# Comm.net
KiCad netlist of a schematic drawn in Altium Designer
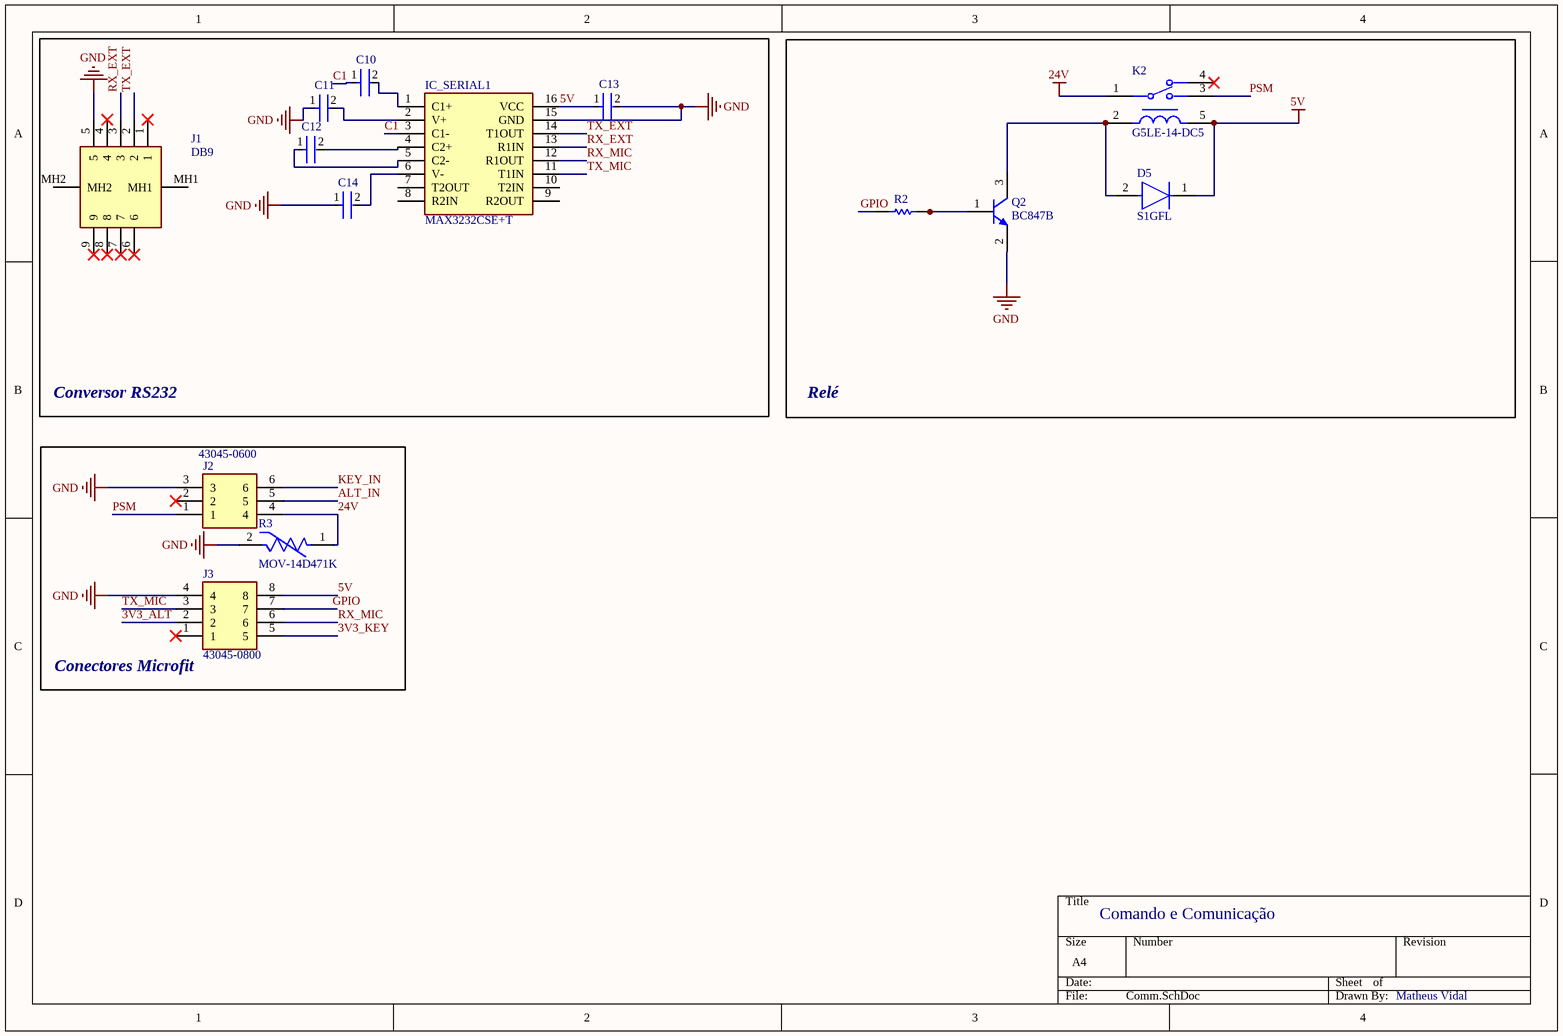
[diagram p0: Comm.SchDoc]

(export (version "E")
  (design (tool "Eeschema 10.0.6"))
  (components
    (comp (ref "C10")
      (value "08055C104J4T2A")
      (footprint "FP-0805-L_2_01_0_2-W_1_25-MFG")
      (description "Automotive Ceramic Capacitor, 0805, 100nF, 5%, X7R, 15%, 50V")
      (fields (field (name "TOLERANCE") "5%"))
      (libsource (lib "Altium Content Vault") (part "02cd4be3c70576c341d710602a673aa"))
    )
    (comp (ref "C11")
      (value "08055C104J4T2A")
      (footprint "FP-0805-L_2_01_0_2-W_1_25-MFG")
      (description "Automotive Ceramic Capacitor, 0805, 100nF, 5%, X7R, 15%, 50V")
      (fields (field (name "TOLERANCE") "5%"))
      (libsource (lib "Altium Content Vault") (part "02cd4be3c70576c341d710602a673aa"))
    )
    (comp (ref "C12")
      (value "08055C104J4T2A")
      (footprint "FP-0805-L_2_01_0_2-W_1_25-MFG")
      (description "Automotive Ceramic Capacitor, 0805, 100nF, 5%, X7R, 15%, 50V")
      (fields (field (name "TOLERANCE") "5%"))
      (libsource (lib "Altium Content Vault") (part "02cd4be3c70576c341d710602a673aa"))
    )
    (comp (ref "C13")
      (value "08055C104J4T2A")
      (footprint "FP-0805-L_2_01_0_2-W_1_25-MFG")
      (description "Automotive Ceramic Capacitor, 0805, 100nF, 5%, X7R, 15%, 50V")
      (fields (field (name "TOLERANCE") "5%"))
      (libsource (lib "Altium Content Vault") (part "02cd4be3c70576c341d710602a673aa"))
    )
    (comp (ref "C14")
      (value "08055C104J4T2A")
      (footprint "FP-0805-L_2_01_0_2-W_1_25-MFG")
      (description "Automotive Ceramic Capacitor, 0805, 100nF, 5%, X7R, 15%, 50V")
      (fields (field (name "TOLERANCE") "5%"))
      (libsource (lib "Altium Content Vault") (part "02cd4be3c70576c341d710602a673aa"))
    )
    (comp (ref "D5")
      (value "S1GFL")
      (footprint "FP-425AD-MFG")
      (description "S1GFL Rectifier Diode, 1 Phase, 1 Element, 1A, 400V V(RRM), Silicon")
      (libsource (lib "Altium Content Vault") (part "e8bb5000357cae87636711d27716c66"))
    )
    (comp (ref "IC_SERIAL1")
      (value "MAX3232CSE+T")
      (footprint "SamacSys:SOIC127P600X175-16N")
      (description "Integrated Circuit")
      (fields (field (name "MOUSER PART NUMBER") "700-MAX3232CSET"))
      (libsource (lib "*") (part "MAX3232CSE+T"))
    )
    (comp (ref "J1")
      (value "DB9")
      (footprint "SamacSys:L77DFE09S1AMN")
      (description "Connector")
      (fields
        (field (name "MANUFACTURER_PART_NUMBER") "L77DFE09S1AMN")
        (field (name "MOUSER PART NUMBER") "523-L77DFE09S1AMN")
      )
      (libsource (lib "*") (part "L77DFE09S1AMN"))
    )
    (comp (ref "J2")
      (value "43045-0600")
      (footprint "SamacSys:43045-06(00,01,02,10)")
      (description "Connector")
      (fields (field (name "MOUSER PART NUMBER") "538-43045-0600"))
      (libsource (lib "*") (part "43045-0600"))
    )
    (comp (ref "J3")
      (value "43045-0800")
      (footprint "SamacSys:43045-08(00,01,02,10)")
      (description "Connector")
      (fields (field (name "MOUSER PART NUMBER") "538-43045-0800"))
      (libsource (lib "*") (part "43045-0800"))
    )
    (comp (ref "K2")
      (value "G5LE-14-DC5")
      (footprint "FP-G5LE-14-DC5-MFG")
      (description "RELAY GEN PURPOSE SPDT 10A 5V")
      (fields
        (field (name "OCTOPART") "https://octopart.com/g5le-14-dc5-omron-28829")
        (field (name "MANUFACTURER") "Omron")
      )
      (libsource (lib "Altium Content Vault") (part "c03b8d08e5d02e70a6880f365e34168"))
    )
    (comp (ref "Q2")
      (value "BC847B")
      (footprint "INF-SOT23_M")
      (description "NPN Silicon AF Transistor, 45 V VCEO, 100 mA IC, SOT23, Reel, Green")
      (fields (field (name "MANUFACTURER") "Infineon"))
      (libsource (lib "Altium Content Vault") (part "INF-BJTNPN-BEC-3"))
    )
    (comp (ref "R2")
      (value "10k")
      (footprint "RESC2013X50X30LL20T20")
      (fields (field (name "MANUFACTURER") "Vishay Dale") (field (name "PART NUMBER") "CRCW08050000Z0EA"))
      (libsource (lib "Altium Content Vault") (part "RES"))
    )
    (comp (ref "R3")
      (value "MOV-14D471K")
      (footprint "FP-MOV-14D471K-MFG")
      (description "VARISTOR 470V 4.5KA DISC 14MM")
      (fields
        (field (name "OCTOPART") "https://octopart.com/mov-14d471k-bourns-21388916")
        (field (name "MANUFACTURER") "Bourns Inc.")
      )
      (libsource (lib "Altium Content Vault") (part "78a88060d5b7b043d6e48adc4284376"))
    )
  )
  (nets
    (net (code "1") (name "/3V3_ALT") (class "Default")
      (node (ref "J3") (pin "2") (pinfunction "2_2") (pintype "passive"))
    )
    (net (code "2") (name "/3V3_KEY") (class "Default")
      (node (ref "J3") (pin "5") (pinfunction "5_5") (pintype "passive"))
    )
    (net (code "3") (name "/ALT_IN") (class "Default")
      (node (ref "J2") (pin "5") (pinfunction "5_5") (pintype "passive"))
    )
    (net (code "4") (name "/C1") (class "Default")
      (node (ref "C10") (pin "1") (pinfunction "1_1") (pintype "passive"))
      (node (ref "IC_SERIAL1") (pin "3") (pinfunction "C1-_3") (pintype "passive"))
    )
    (net (code "5") (name "/GPIO") (class "Default")
      (node (ref "J3") (pin "7") (pinfunction "7_7") (pintype "passive"))
      (node (ref "R2") (pin "2") (pinfunction "2_2") (pintype "passive"))
    )
    (net (code "6") (name "/KEY_IN") (class "Default")
      (node (ref "J2") (pin "6") (pinfunction "6_6") (pintype "passive"))
    )
    (net (code "7") (name "/PSM") (class "Default")
      (node (ref "J2") (pin "1") (pinfunction "1_1") (pintype "passive"))
      (node (ref "K2") (pin "3") (pinfunction "3_3") (pintype "passive"))
    )
    (net (code "8") (name "/RX_EXT") (class "Default")
      (node (ref "IC_SERIAL1") (pin "13") (pinfunction "R1IN_13") (pintype "passive"))
      (node (ref "J1") (pin "3") (pinfunction "3_3") (pintype "passive"))
    )
    (net (code "9") (name "/RX_MIC") (class "Default")
      (node (ref "IC_SERIAL1") (pin "12") (pinfunction "R1OUT_12") (pintype "passive"))
      (node (ref "J3") (pin "6") (pinfunction "6_6") (pintype "passive"))
    )
    (net (code "10") (name "/TX_EXT") (class "Default")
      (node (ref "IC_SERIAL1") (pin "14") (pinfunction "T1OUT_14") (pintype "passive"))
      (node (ref "J1") (pin "2") (pinfunction "2_2") (pintype "passive"))
    )
    (net (code "11") (name "/TX_MIC") (class "Default")
      (node (ref "IC_SERIAL1") (pin "11") (pinfunction "T1IN_11") (pintype "passive"))
      (node (ref "J3") (pin "3") (pinfunction "3_3") (pintype "passive"))
    )
    (net (code "12") (name "5V") (class "Default")
      (node (ref "C13") (pin "1") (pinfunction "1_1") (pintype "passive"))
      (node (ref "D5") (pin "1") (pinfunction "C_1") (pintype "passive"))
      (node (ref "IC_SERIAL1") (pin "16") (pinfunction "VCC_16") (pintype "passive"))
      (node (ref "J3") (pin "8") (pinfunction "8_8") (pintype "passive"))
      (node (ref "K2") (pin "5") (pinfunction "5_5") (pintype "passive"))
    )
    (net (code "13") (name "24V") (class "Default")
      (node (ref "J2") (pin "4") (pinfunction "4_4") (pintype "passive"))
      (node (ref "K2") (pin "1") (pinfunction "1_1") (pintype "passive"))
      (node (ref "R3") (pin "1") (pinfunction "1_1") (pintype "passive"))
    )
    (net (code "14") (name "GND") (class "Default")
      (node (ref "C11") (pin "1") (pinfunction "1_1") (pintype "passive"))
      (node (ref "C13") (pin "2") (pinfunction "2_2") (pintype "passive"))
      (node (ref "C14") (pin "1") (pinfunction "1_1") (pintype "passive"))
      (node (ref "IC_SERIAL1") (pin "15") (pinfunction "GND_15") (pintype "passive"))
      (node (ref "J1") (pin "5") (pinfunction "5_5") (pintype "passive"))
      (node (ref "J2") (pin "3") (pinfunction "3_3") (pintype "passive"))
      (node (ref "J3") (pin "4") (pinfunction "4_4") (pintype "passive"))
      (node (ref "Q2") (pin "2") (pinfunction "E_2") (pintype "passive"))
      (node (ref "R3") (pin "2") (pinfunction "2_2") (pintype "passive"))
    )
    (net (code "15") (name "Net-(D5-A)") (class "Default")
      (node (ref "D5") (pin "2") (pinfunction "A_2") (pintype "passive"))
      (node (ref "K2") (pin "2") (pinfunction "2_2") (pintype "passive"))
      (node (ref "Q2") (pin "3") (pinfunction "C_3") (pintype "passive"))
    )
    (net (code "16") (name "Net-(IC_SERIAL1-C1+)") (class "Default")
      (node (ref "C10") (pin "2") (pinfunction "2_2") (pintype "passive"))
      (node (ref "IC_SERIAL1") (pin "1") (pinfunction "C1+_1") (pintype "passive"))
    )
    (net (code "17") (name "Net-(IC_SERIAL1-C2+)") (class "Default")
      (node (ref "C12") (pin "2") (pinfunction "2_2") (pintype "passive"))
      (node (ref "IC_SERIAL1") (pin "4") (pinfunction "C2+_4") (pintype "passive"))
    )
    (net (code "18") (name "Net-(IC_SERIAL1-C2-)") (class "Default")
      (node (ref "C12") (pin "1") (pinfunction "1_1") (pintype "passive"))
      (node (ref "IC_SERIAL1") (pin "5") (pinfunction "C2-_5") (pintype "passive"))
    )
    (net (code "19") (name "Net-(IC_SERIAL1-V+)") (class "Default")
      (node (ref "C11") (pin "2") (pinfunction "2_2") (pintype "passive"))
      (node (ref "IC_SERIAL1") (pin "2") (pinfunction "V+_2") (pintype "passive"))
    )
    (net (code "20") (name "Net-(IC_SERIAL1-V-)") (class "Default")
      (node (ref "C14") (pin "2") (pinfunction "2_2") (pintype "passive"))
      (node (ref "IC_SERIAL1") (pin "6") (pinfunction "V-_6") (pintype "passive"))
    )
    (net (code "21") (name "Net-(Q2-B)") (class "Default")
      (node (ref "Q2") (pin "1") (pinfunction "B_1") (pintype "passive"))
      (node (ref "R2") (pin "1") (pinfunction "1_1") (pintype "passive"))
    )
    (net (code "22") (name "unconnected-(IC_SERIAL1-R2IN-Pad8)") (class "Default")
      (node (ref "IC_SERIAL1") (pin "8") (pinfunction "R2IN_8") (pintype "passive"))
    )
    (net (code "23") (name "unconnected-(IC_SERIAL1-R2OUT-Pad9)") (class "Default")
      (node (ref "IC_SERIAL1") (pin "9") (pinfunction "R2OUT_9") (pintype "passive"))
    )
    (net (code "24") (name "unconnected-(IC_SERIAL1-T2IN-Pad10)") (class "Default")
      (node (ref "IC_SERIAL1") (pin "10") (pinfunction "T2IN_10") (pintype "passive"))
    )
    (net (code "25") (name "unconnected-(IC_SERIAL1-T2OUT-Pad7)") (class "Default")
      (node (ref "IC_SERIAL1") (pin "7") (pinfunction "T2OUT_7") (pintype "passive"))
    )
    (net (code "26") (name "unconnected-(J1-Pad1)") (class "Default")
      (node (ref "J1") (pin "1") (pinfunction "1_1") (pintype "passive+no_connect"))
    )
    (net (code "27") (name "unconnected-(J1-Pad4)") (class "Default")
      (node (ref "J1") (pin "4") (pinfunction "4_4") (pintype "passive+no_connect"))
    )
    (net (code "28") (name "unconnected-(J1-Pad6)") (class "Default")
      (node (ref "J1") (pin "6") (pinfunction "6_6") (pintype "passive+no_connect"))
    )
    (net (code "29") (name "unconnected-(J1-Pad7)") (class "Default")
      (node (ref "J1") (pin "7") (pinfunction "7_7") (pintype "passive+no_connect"))
    )
    (net (code "30") (name "unconnected-(J1-Pad8)") (class "Default")
      (node (ref "J1") (pin "8") (pinfunction "8_8") (pintype "passive+no_connect"))
    )
    (net (code "31") (name "unconnected-(J1-Pad9)") (class "Default")
      (node (ref "J1") (pin "9") (pinfunction "9_9") (pintype "passive+no_connect"))
    )
    (net (code "32") (name "unconnected-(J1-PadMH1)") (class "Default")
      (node (ref "J1") (pin "MH1") (pinfunction "MH1_MH1") (pintype "passive"))
    )
    (net (code "33") (name "unconnected-(J1-PadMH2)") (class "Default")
      (node (ref "J1") (pin "MH2") (pinfunction "MH2_MH2") (pintype "passive"))
    )
    (net (code "34") (name "unconnected-(J2-Pad2)") (class "Default")
      (node (ref "J2") (pin "2") (pinfunction "2_2") (pintype "passive+no_connect"))
    )
    (net (code "35") (name "unconnected-(J3-Pad1)") (class "Default")
      (node (ref "J3") (pin "1") (pinfunction "1_1") (pintype "passive+no_connect"))
    )
    (net (code "36") (name "unconnected-(K2-Pad4)") (class "Default")
      (node (ref "K2") (pin "4") (pinfunction "4_4") (pintype "passive+no_connect"))
    )
  )
)
